# v1.net
KiCad netlist of a schematic drawn in EasyEDA Pro
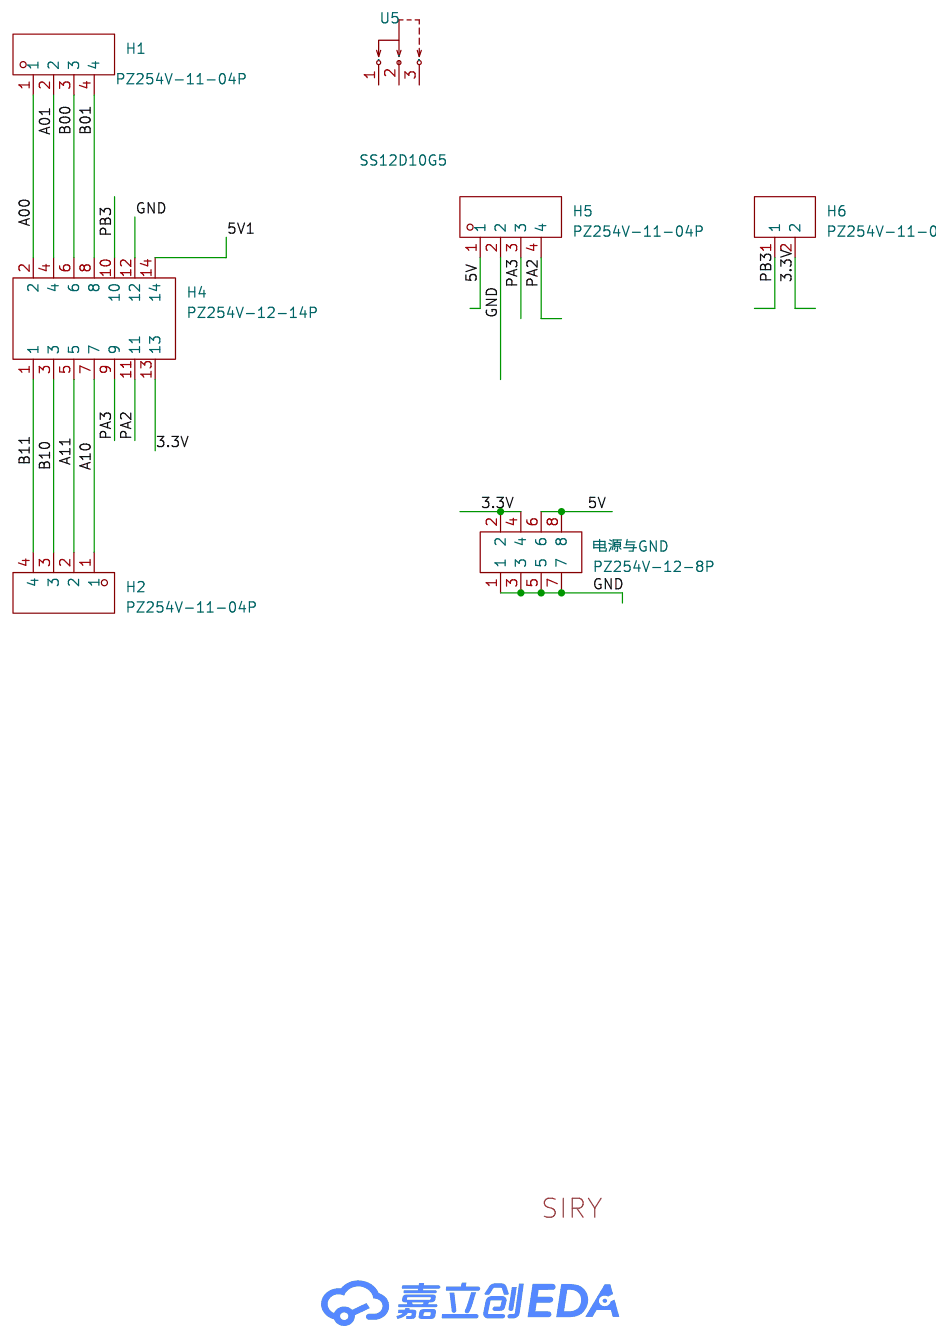
[diagram p0: schematic sheet]

(export (version "E")
  (design (tool "Eeschema 10.0.6"))
  (components
    (comp (ref "H1")
      (value "PZ254V-11-04P")
      (footprint "easyedapro:HDR-TH_4P-P2.54-V-M")
      (fields (field (name "Manufacturer") "XFCN(兴飞)"))
      (libsource (lib "easyedapro") (part "PZ254V-11-04P_C2691448"))
    )
    (comp (ref "H2")
      (value "PZ254V-11-04P")
      (footprint "easyedapro:HDR-TH_4P-P2.54-V-M")
      (fields (field (name "Manufacturer") "XFCN(兴飞)"))
      (libsource (lib "easyedapro") (part "PZ254V-11-04P_C2691448"))
    )
    (comp (ref "H4")
      (value "PZ254V-12-14P")
      (footprint "easyedapro:HDR-TH_14P-P2.54-V-M-R2-C7-S2.54")
      (fields (field (name "Manufacturer") "XFCN(兴飞)"))
      (libsource (lib "easyedapro") (part "PZ254V-12-14P"))
    )
    (comp (ref "H5")
      (value "PZ254V-11-04P")
      (footprint "easyedapro:HDR-TH_4P-P2.54-V-M")
      (fields (field (name "Manufacturer") "XFCN(兴飞)"))
      (libsource (lib "easyedapro") (part "PZ254V-11-04P_C2691448"))
    )
    (comp (ref "H6")
      (value "PZ254V-11-02P")
      (footprint "easyedapro:HDR-TH_2P-P2.54-V-M")
      (fields (field (name "Manufacturer") "XFCN(兴飞)"))
      (libsource (lib "easyedapro") (part "PZ254V-11-02P"))
    )
    (comp (ref "U5")
      (value "SS12D10G5")
      (footprint "easyedapro:SW-TH_SHOU-HAN_SS12D10G4")
      (description "电路结构:单刀双掷;安装方式:直插;额定电流(DC):2A;额定电压(DC):125V;机械寿命:3千次;")
      (fields (field (name "Manufacturer") "SHOU HAN(首韩)"))
      (libsource (lib "easyedapro") (part "SS12D10G5"))
    )
    (comp (ref "电源与GND")
      (value "PZ254V-12-8P")
      (footprint "easyedapro:HDR-TH_8P-P2.54-V-M-R2-C4-S2.54")
      (fields (field (name "Manufacturer") "XFCN(兴飞)"))
      (libsource (lib "easyedapro") (part "PZ254V-12-8P"))
    )
  )
  (nets
    (net (code "1") (name "/3.3V") (class "Default")
      (node (ref "H4") (pin "13") (pinfunction "13_13") (pintype "unspecified"))
      (node (ref "H6") (pin "2") (pinfunction "2_2") (pintype "unspecified"))
      (node (ref "电源与GND") (pin "2") (pinfunction "2_2") (pintype "unspecified"))
      (node (ref "电源与GND") (pin "4") (pinfunction "4_4") (pintype "unspecified"))
    )
    (net (code "2") (name "/5V") (class "Default")
      (node (ref "H5") (pin "1") (pinfunction "1_1") (pintype "unspecified"))
      (node (ref "电源与GND") (pin "6") (pinfunction "6_6") (pintype "unspecified"))
      (node (ref "电源与GND") (pin "8") (pinfunction "8_8") (pintype "unspecified"))
    )
    (net (code "3") (name "/5V1") (class "Default")
      (node (ref "H4") (pin "14") (pinfunction "14_14") (pintype "unspecified"))
    )
    (net (code "4") (name "/A00") (class "Default")
      (node (ref "H1") (pin "1") (pinfunction "1_1") (pintype "unspecified"))
      (node (ref "H4") (pin "2") (pinfunction "2_2") (pintype "unspecified"))
    )
    (net (code "5") (name "/A01") (class "Default")
      (node (ref "H1") (pin "2") (pinfunction "2_2") (pintype "unspecified"))
      (node (ref "H4") (pin "4") (pinfunction "4_4") (pintype "unspecified"))
    )
    (net (code "6") (name "/A10") (class "Default")
      (node (ref "H2") (pin "1") (pinfunction "1_1") (pintype "unspecified"))
      (node (ref "H4") (pin "7") (pinfunction "7_7") (pintype "unspecified"))
    )
    (net (code "7") (name "/A11") (class "Default")
      (node (ref "H2") (pin "2") (pinfunction "2_2") (pintype "unspecified"))
      (node (ref "H4") (pin "5") (pinfunction "5_5") (pintype "unspecified"))
    )
    (net (code "8") (name "/B00") (class "Default")
      (node (ref "H1") (pin "3") (pinfunction "3_3") (pintype "unspecified"))
      (node (ref "H4") (pin "6") (pinfunction "6_6") (pintype "unspecified"))
    )
    (net (code "9") (name "/B01") (class "Default")
      (node (ref "H1") (pin "4") (pinfunction "4_4") (pintype "unspecified"))
      (node (ref "H4") (pin "8") (pinfunction "8_8") (pintype "unspecified"))
    )
    (net (code "10") (name "/B10") (class "Default")
      (node (ref "H2") (pin "3") (pinfunction "3_3") (pintype "unspecified"))
      (node (ref "H4") (pin "3") (pinfunction "3_3") (pintype "unspecified"))
    )
    (net (code "11") (name "/B11") (class "Default")
      (node (ref "H2") (pin "4") (pinfunction "4_4") (pintype "unspecified"))
      (node (ref "H4") (pin "1") (pinfunction "1_1") (pintype "unspecified"))
    )
    (net (code "12") (name "/GND") (class "Default")
      (node (ref "H4") (pin "12") (pinfunction "12_12") (pintype "unspecified"))
      (node (ref "H5") (pin "2") (pinfunction "2_2") (pintype "unspecified"))
      (node (ref "电源与GND") (pin "1") (pinfunction "1_1") (pintype "unspecified"))
      (node (ref "电源与GND") (pin "3") (pinfunction "3_3") (pintype "unspecified"))
      (node (ref "电源与GND") (pin "5") (pinfunction "5_5") (pintype "unspecified"))
      (node (ref "电源与GND") (pin "7") (pinfunction "7_7") (pintype "unspecified"))
    )
    (net (code "13") (name "/PA2") (class "Default")
      (node (ref "H4") (pin "11") (pinfunction "11_11") (pintype "unspecified"))
      (node (ref "H5") (pin "4") (pinfunction "4_4") (pintype "unspecified"))
    )
    (net (code "14") (name "/PA3") (class "Default")
      (node (ref "H4") (pin "9") (pinfunction "9_9") (pintype "unspecified"))
      (node (ref "H5") (pin "3") (pinfunction "3_3") (pintype "unspecified"))
    )
    (net (code "15") (name "/PB3") (class "Default")
      (node (ref "H4") (pin "10") (pinfunction "10_10") (pintype "unspecified"))
      (node (ref "H6") (pin "1") (pinfunction "1_1") (pintype "unspecified"))
    )
    (net (code "16") (name "unconnected-(U5-Pad1)") (class "Default")
      (node (ref "U5") (pin "1") (pinfunction "1_1") (pintype "unspecified"))
    )
    (net (code "17") (name "unconnected-(U5-Pad2)") (class "Default")
      (node (ref "U5") (pin "2") (pinfunction "2_2") (pintype "unspecified"))
    )
    (net (code "18") (name "unconnected-(U5-Pad3)") (class "Default")
      (node (ref "U5") (pin "3") (pinfunction "3_3") (pintype "unspecified"))
    )
  )
)
